# VoltageSense.net
KiCad netlist of a schematic drawn in Altium Designer
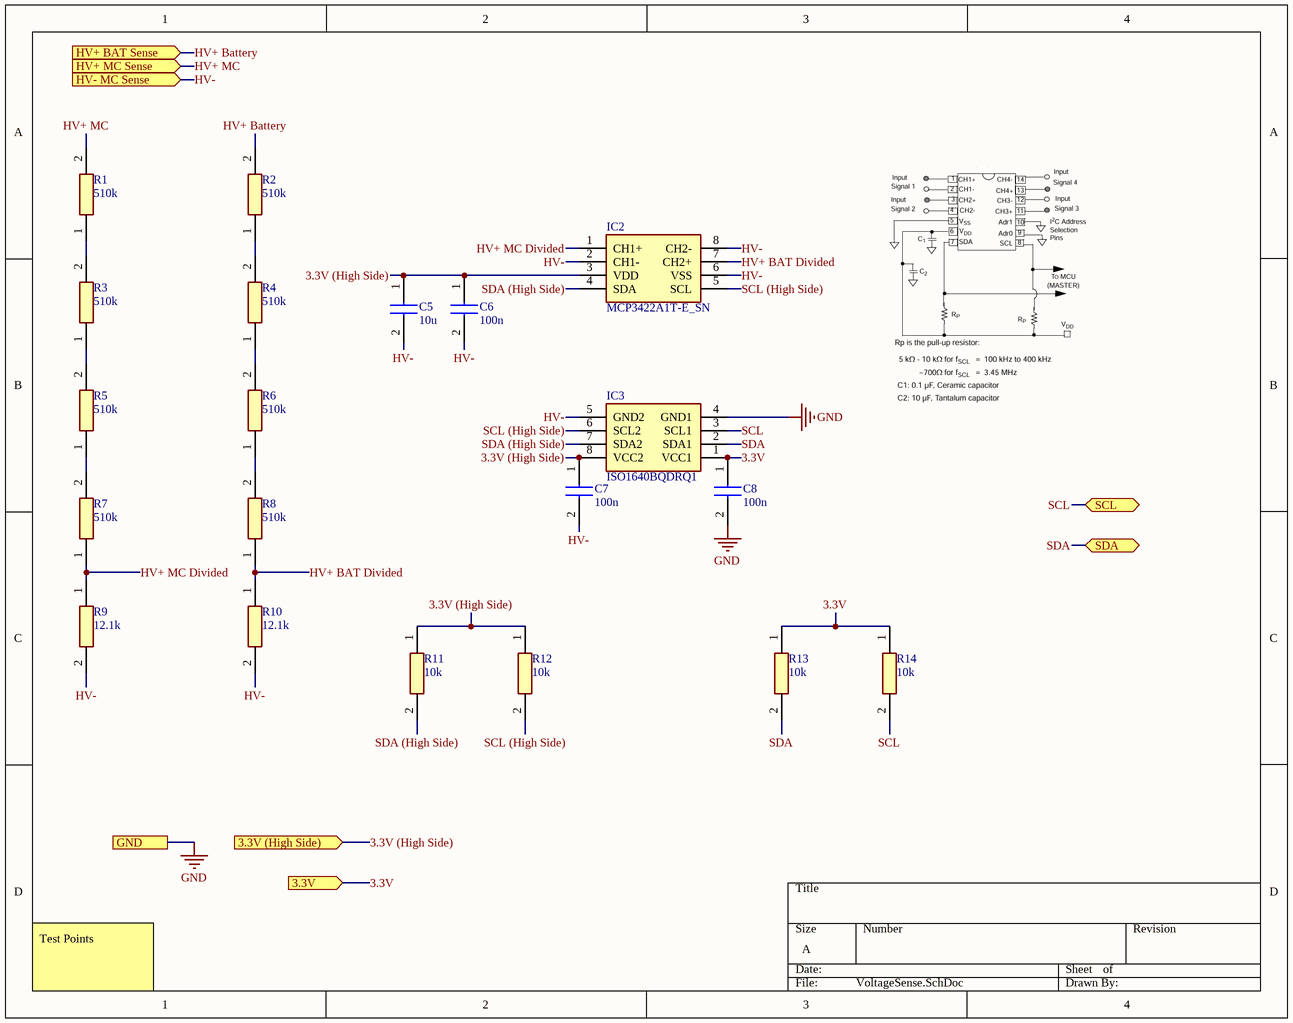
[diagram p0: VoltageSense.SchDoc]

(export (version "E")
  (design (tool "Eeschema 10.0.6"))
  (components
    (comp (ref "C5")
      (value "10u")
      (footprint "CAPC1608X90N")
      (description "Capacitor")
      (fields (field (name "MANUFACTURER_PART_NUMBER") "CL10A106KQ8NNNL"))
      (libsource (lib "SamacSys") (part "CL10A106KQ8NNNL"))
    )
    (comp (ref "C6")
      (value "100n")
      (footprint "CAPC1608X90N")
      (description "Capacitor")
      (fields
        (field (name "MANUFACTURER_PART_NUMBER") "06035C104J4Z2A")
        (field (name "MOUSER PART NUMBER") "581-06035C104J4Z2A")
      )
      (libsource (lib "SamacSys") (part "06035C104J4Z2A"))
    )
    (comp (ref "C7")
      (value "100n")
      (footprint "CAPC3216X94N")
      (description "Capacitor")
      (fields
        (field (name "MANUFACTURER_PART_NUMBER") "12065C104J4Z2A")
        (field (name "MOUSER PART NUMBER") "581-12065C104J4Z2A")
      )
      (libsource (lib "SamacSys") (part "12065C104J4Z2A"))
    )
    (comp (ref "C8")
      (value "100n")
      (footprint "CAPC3216X94N")
      (description "Capacitor")
      (fields
        (field (name "MANUFACTURER_PART_NUMBER") "12065C104J4Z2A")
        (field (name "MOUSER PART NUMBER") "581-12065C104J4Z2A")
      )
      (libsource (lib "SamacSys") (part "12065C104J4Z2A"))
    )
    (comp (ref "IC2")
      (value "MCP3422A1T-E_SN")
      (footprint "SOIC127P600X175-8N")
      (description "Integrated Circuit")
      (fields
        (field (name "MANUFACTURER_PART_NUMBER") "MCP3422A1T-E/SN")
        (field (name "MOUSER PART NUMBER") "579-MCP3422A1T-E/SN")
      )
      (libsource (lib "SamacSys") (part "MCP3422A1T-E_SN"))
    )
    (comp (ref "IC3")
      (value "ISO1640BQDRQ1")
      (footprint "SamacSys:SOIC127P600X175-8N")
      (description "Integrated Circuit")
      (fields (field (name "MOUSER PART NUMBER") "595-ISO1640BQDRQ1"))
      (libsource (lib "SamacSys") (part "ISO1640BQDRQ1"))
    )
    (comp (ref "R1")
      (value "510k")
      (footprint "RESC3216X75N")
      (description "Resistor")
      (fields
        (field (name "MANUFACTURER_PART_NUMBER") "CR1206-FX-5103ELF")
        (field (name "MOUSER PART NUMBER") "652-CR1206FX-5103ELF")
      )
      (libsource (lib "SamacSys") (part "CR1206-FX-5103ELF"))
    )
    (comp (ref "R2")
      (value "510k")
      (footprint "RESC3216X75N")
      (description "Resistor")
      (fields
        (field (name "MANUFACTURER_PART_NUMBER") "CR1206-FX-5103ELF")
        (field (name "MOUSER PART NUMBER") "652-CR1206FX-5103ELF")
      )
      (libsource (lib "SamacSys") (part "CR1206-FX-5103ELF"))
    )
    (comp (ref "R3")
      (value "510k")
      (footprint "RESC3216X75N")
      (description "Resistor")
      (fields
        (field (name "MANUFACTURER_PART_NUMBER") "CR1206-FX-5103ELF")
        (field (name "MOUSER PART NUMBER") "652-CR1206FX-5103ELF")
      )
      (libsource (lib "SamacSys") (part "CR1206-FX-5103ELF"))
    )
    (comp (ref "R4")
      (value "510k")
      (footprint "RESC3216X75N")
      (description "Resistor")
      (fields
        (field (name "MANUFACTURER_PART_NUMBER") "CR1206-FX-5103ELF")
        (field (name "MOUSER PART NUMBER") "652-CR1206FX-5103ELF")
      )
      (libsource (lib "SamacSys") (part "CR1206-FX-5103ELF"))
    )
    (comp (ref "R5")
      (value "510k")
      (footprint "RESC3216X75N")
      (description "Resistor")
      (fields
        (field (name "MANUFACTURER_PART_NUMBER") "CR1206-FX-5103ELF")
        (field (name "MOUSER PART NUMBER") "652-CR1206FX-5103ELF")
      )
      (libsource (lib "SamacSys") (part "CR1206-FX-5103ELF"))
    )
    (comp (ref "R6")
      (value "510k")
      (footprint "RESC3216X75N")
      (description "Resistor")
      (fields
        (field (name "MANUFACTURER_PART_NUMBER") "CR1206-FX-5103ELF")
        (field (name "MOUSER PART NUMBER") "652-CR1206FX-5103ELF")
      )
      (libsource (lib "SamacSys") (part "CR1206-FX-5103ELF"))
    )
    (comp (ref "R7")
      (value "510k")
      (footprint "RESC3216X75N")
      (description "Resistor")
      (fields
        (field (name "MANUFACTURER_PART_NUMBER") "CR1206-FX-5103ELF")
        (field (name "MOUSER PART NUMBER") "652-CR1206FX-5103ELF")
      )
      (libsource (lib "SamacSys") (part "CR1206-FX-5103ELF"))
    )
    (comp (ref "R8")
      (value "510k")
      (footprint "RESC3216X75N")
      (description "Resistor")
      (fields
        (field (name "MANUFACTURER_PART_NUMBER") "CR1206-FX-5103ELF")
        (field (name "MOUSER PART NUMBER") "652-CR1206FX-5103ELF")
      )
      (libsource (lib "SamacSys") (part "CR1206-FX-5103ELF"))
    )
    (comp (ref "R9")
      (value "12.1k")
      (footprint "ERJS08_U08_(1206)")
      (description "Resistor")
      (fields
        (field (name "MANUFACTURER_PART_NUMBER") "ERJ-S08F1212V")
        (field (name "MOUSER PART NUMBER") "667-ERJ-S08F1212V")
      )
      (libsource (lib "SamacSys") (part "ERJ-S08F1212V"))
    )
    (comp (ref "R10")
      (value "12.1k")
      (footprint "ERJS08_U08_(1206)")
      (description "Resistor")
      (fields
        (field (name "MANUFACTURER_PART_NUMBER") "ERJ-S08F1212V")
        (field (name "MOUSER PART NUMBER") "667-ERJ-S08F1212V")
      )
      (libsource (lib "SamacSys") (part "ERJ-S08F1212V"))
    )
    (comp (ref "R11")
      (value "10k")
      (footprint "RESC1608X55N")
      (description "Resistor")
      (fields
        (field (name "MANUFACTURER_PART_NUMBER") "CRGCQ0603F10K")
        (field (name "MOUSER PART NUMBER") "279-CRGCQ0603F10K")
      )
      (libsource (lib "SamacSys") (part "CRGCQ0603F10K"))
    )
    (comp (ref "R12")
      (value "10k")
      (footprint "RESC1608X55N")
      (description "Resistor")
      (fields
        (field (name "MANUFACTURER_PART_NUMBER") "CRGCQ0603F10K")
        (field (name "MOUSER PART NUMBER") "279-CRGCQ0603F10K")
      )
      (libsource (lib "SamacSys") (part "CRGCQ0603F10K"))
    )
    (comp (ref "R13")
      (value "10k")
      (footprint "RESC1608X55N")
      (description "Resistor")
      (fields
        (field (name "MANUFACTURER_PART_NUMBER") "CRGCQ0603F10K")
        (field (name "MOUSER PART NUMBER") "279-CRGCQ0603F10K")
      )
      (libsource (lib "SamacSys") (part "CRGCQ0603F10K"))
    )
    (comp (ref "R14")
      (value "10k")
      (footprint "RESC1608X55N")
      (description "Resistor")
      (fields
        (field (name "MANUFACTURER_PART_NUMBER") "CRGCQ0603F10K")
        (field (name "MOUSER PART NUMBER") "279-CRGCQ0603F10K")
      )
      (libsource (lib "SamacSys") (part "CRGCQ0603F10K"))
    )
  )
  (nets
    (net (code "1") (name "/3.3V") (class "Default")
      (node (ref "C8") (pin "1") (pinfunction "1_1") (pintype "passive"))
      (node (ref "IC3") (pin "1") (pinfunction "VCC1_1") (pintype "passive"))
      (node (ref "R13") (pin "1") (pinfunction "1_1") (pintype "passive"))
      (node (ref "R14") (pin "1") (pinfunction "1_1") (pintype "passive"))
    )
    (net (code "2") (name "/3.3V (High Side)") (class "Default")
      (node (ref "C5") (pin "1") (pinfunction "1_1") (pintype "passive"))
      (node (ref "C6") (pin "1") (pinfunction "1_1") (pintype "passive"))
      (node (ref "C7") (pin "1") (pinfunction "1_1") (pintype "passive"))
      (node (ref "IC2") (pin "3") (pinfunction "VDD_3") (pintype "passive"))
      (node (ref "IC3") (pin "8") (pinfunction "VCC2_8") (pintype "passive"))
      (node (ref "R11") (pin "1") (pinfunction "1_1") (pintype "passive"))
      (node (ref "R12") (pin "1") (pinfunction "1_1") (pintype "passive"))
    )
    (net (code "3") (name "/HV+ BAT Divided") (class "Default")
      (node (ref "IC2") (pin "7") (pinfunction "CH2+_7") (pintype "passive"))
      (node (ref "R10") (pin "1") (pinfunction "1_1") (pintype "passive"))
      (node (ref "R8") (pin "1") (pinfunction "1_1") (pintype "passive"))
    )
    (net (code "4") (name "/HV+ Battery") (class "Default")
      (node (ref "R2") (pin "2") (pinfunction "2_2") (pintype "passive"))
    )
    (net (code "5") (name "/HV+ MC") (class "Default")
      (node (ref "R1") (pin "2") (pinfunction "2_2") (pintype "passive"))
    )
    (net (code "6") (name "/HV+ MC Divided") (class "Default")
      (node (ref "IC2") (pin "1") (pinfunction "CH1+_1") (pintype "passive"))
      (node (ref "R7") (pin "1") (pinfunction "1_1") (pintype "passive"))
      (node (ref "R9") (pin "1") (pinfunction "1_1") (pintype "passive"))
    )
    (net (code "7") (name "/HV-") (class "Default")
      (node (ref "C5") (pin "2") (pinfunction "2_2") (pintype "passive"))
      (node (ref "C6") (pin "2") (pinfunction "2_2") (pintype "passive"))
      (node (ref "C7") (pin "2") (pinfunction "2_2") (pintype "passive"))
      (node (ref "IC2") (pin "2") (pinfunction "CH1-_2") (pintype "passive"))
      (node (ref "IC2") (pin "6") (pinfunction "VSS_6") (pintype "passive"))
      (node (ref "IC2") (pin "8") (pinfunction "CH2-_8") (pintype "passive"))
      (node (ref "IC3") (pin "5") (pinfunction "GND2_5") (pintype "passive"))
      (node (ref "R10") (pin "2") (pinfunction "2_2") (pintype "passive"))
      (node (ref "R9") (pin "2") (pinfunction "2_2") (pintype "passive"))
    )
    (net (code "8") (name "/SCL") (class "Default")
      (node (ref "IC3") (pin "3") (pinfunction "SCL1_3") (pintype "passive"))
      (node (ref "R14") (pin "2") (pinfunction "2_2") (pintype "passive"))
    )
    (net (code "9") (name "/SCL (High Side)") (class "Default")
      (node (ref "IC2") (pin "5") (pinfunction "SCL_5") (pintype "passive"))
      (node (ref "IC3") (pin "6") (pinfunction "SCL2_6") (pintype "passive"))
      (node (ref "R12") (pin "2") (pinfunction "2_2") (pintype "passive"))
    )
    (net (code "10") (name "/SDA") (class "Default")
      (node (ref "IC3") (pin "2") (pinfunction "SDA1_2") (pintype "passive"))
      (node (ref "R13") (pin "2") (pinfunction "2_2") (pintype "passive"))
    )
    (net (code "11") (name "/SDA (High Side)") (class "Default")
      (node (ref "IC2") (pin "4") (pinfunction "SDA_4") (pintype "passive"))
      (node (ref "IC3") (pin "7") (pinfunction "SDA2_7") (pintype "passive"))
      (node (ref "R11") (pin "2") (pinfunction "2_2") (pintype "passive"))
    )
    (net (code "12") (name "GND") (class "Default")
      (node (ref "C8") (pin "2") (pinfunction "2_2") (pintype "passive"))
      (node (ref "IC3") (pin "4") (pinfunction "GND1_4") (pintype "passive"))
    )
    (net (code "13") (name "Net-(R1-Pad1)") (class "Default")
      (node (ref "R1") (pin "1") (pinfunction "1_1") (pintype "passive"))
      (node (ref "R3") (pin "2") (pinfunction "2_2") (pintype "passive"))
    )
    (net (code "14") (name "Net-(R2-Pad1)") (class "Default")
      (node (ref "R2") (pin "1") (pinfunction "1_1") (pintype "passive"))
      (node (ref "R4") (pin "2") (pinfunction "2_2") (pintype "passive"))
    )
    (net (code "15") (name "Net-(R3-Pad1)") (class "Default")
      (node (ref "R3") (pin "1") (pinfunction "1_1") (pintype "passive"))
      (node (ref "R5") (pin "2") (pinfunction "2_2") (pintype "passive"))
    )
    (net (code "16") (name "Net-(R4-Pad1)") (class "Default")
      (node (ref "R4") (pin "1") (pinfunction "1_1") (pintype "passive"))
      (node (ref "R6") (pin "2") (pinfunction "2_2") (pintype "passive"))
    )
    (net (code "17") (name "Net-(R5-Pad1)") (class "Default")
      (node (ref "R5") (pin "1") (pinfunction "1_1") (pintype "passive"))
      (node (ref "R7") (pin "2") (pinfunction "2_2") (pintype "passive"))
    )
    (net (code "18") (name "Net-(R6-Pad1)") (class "Default")
      (node (ref "R6") (pin "1") (pinfunction "1_1") (pintype "passive"))
      (node (ref "R8") (pin "2") (pinfunction "2_2") (pintype "passive"))
    )
  )
)
